# MB_Nano_V3_2.net
KiCad netlist of a schematic drawn in EAGLE
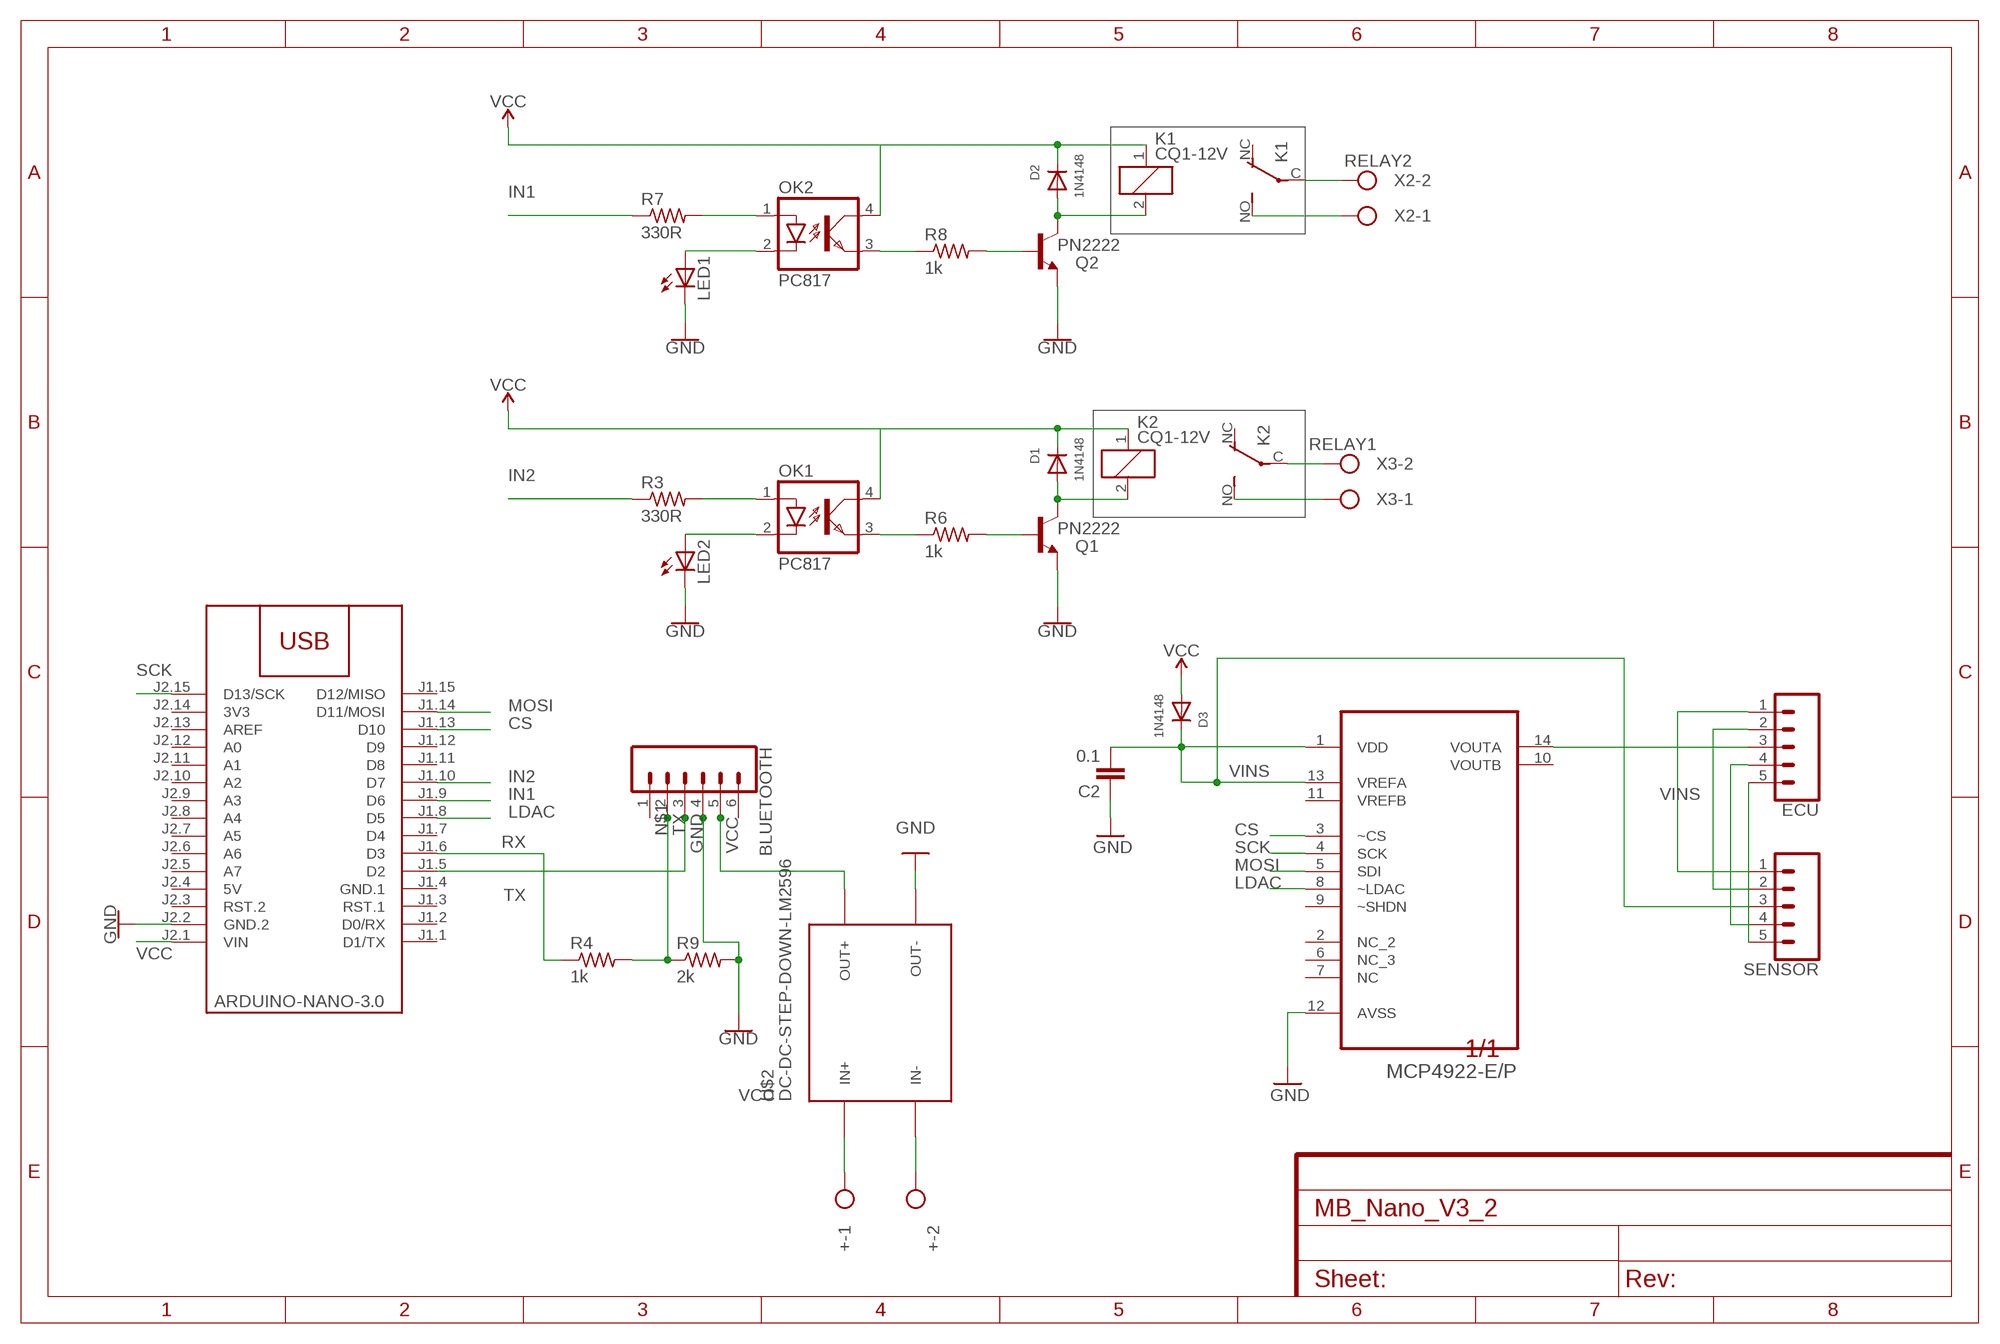
[diagram p0: schematic, sheet 1]

(export (version "E")
  (design (tool "Eeschema 10.0.6"))
  (components
    (comp (ref "+")
      (value "Vcc")
      (footprint "eagle-import:W237-102")
      (fields (field (name "MPN") "237-102"))
      (libsource (lib "eagle-import") (part "W237-102"))
    )
    (comp (ref "BLUETOOTH")
      (value "CONN_06LONGPADS")
      (footprint "eagle-import:1X06_LONGPADS")
      (libsource (lib "eagle-import") (part "CONN_06LONGPADS"))
    )
    (comp (ref "C2")
      (value "0.1")
      (footprint "eagle-import:CAP-PTH-5MM")
      (libsource (lib "eagle-import") (part "CAPPTH1"))
    )
    (comp (ref "D1")
      (value "1N4148")
      (footprint "eagle-import:DO-1N4148")
      (libsource (lib "eagle-import") (part "DIODEDO-1N4148"))
    )
    (comp (ref "D2")
      (value "1N4148")
      (footprint "eagle-import:DO-1N4148")
      (libsource (lib "eagle-import") (part "DIODEDO-1N4148"))
    )
    (comp (ref "D3")
      (value "1N4148")
      (footprint "eagle-import:DO-1N4148")
      (libsource (lib "eagle-import") (part "DIODEDO-1N4148"))
    )
    (comp (ref "ECU")
      (value "CONN_05PTH_LONGPADS")
      (footprint "eagle-import:1X05_LONGPADS")
      (libsource (lib "eagle-import") (part "CONN_05PTH_LONGPADS"))
    )
    (comp (ref "K1")
      (value "CQ1-12V")
      (footprint "eagle-import:CQ1")
      (libsource (lib "eagle-import") (part "CQ1-12V"))
    )
    (comp (ref "K2")
      (value "CQ1-12V")
      (footprint "eagle-import:CQ1")
      (libsource (lib "eagle-import") (part "CQ1-12V"))
    )
    (comp (ref "LED1")
      (value "LED3MM")
      (footprint "eagle-import:LED3MM")
      (libsource (lib "eagle-import") (part "LED3MM"))
    )
    (comp (ref "LED2")
      (value "LED3MM")
      (footprint "eagle-import:LED3MM")
      (libsource (lib "eagle-import") (part "LED3MM"))
    )
    (comp (ref "M2")
      (value "ARDUINO-NANO-3.0")
      (footprint "eagle-import:ARDUINO-NANO-3.0")
      (libsource (lib "eagle-import") (part "ARDUINO-NANO-3.0"))
    )
    (comp (ref "OK1")
      (value "PC817")
      (footprint "eagle-import:DIL04")
      (fields (field (name "MPN") "PC817X4J000F"))
      (libsource (lib "eagle-import") (part "PC817"))
    )
    (comp (ref "OK2")
      (value "PC817")
      (footprint "eagle-import:DIL04")
      (fields (field (name "MPN") "PC817X4J000F"))
      (libsource (lib "eagle-import") (part "PC817"))
    )
    (comp (ref "Q1")
      (value "PN2222")
      (footprint "eagle-import:TO92-EBC")
      (libsource (lib "eagle-import") (part "BC447"))
    )
    (comp (ref "Q2")
      (value "PN2222")
      (footprint "eagle-import:TO92-EBC")
      (libsource (lib "eagle-import") (part "BC447"))
    )
    (comp (ref "R3")
      (value "330R")
      (footprint "eagle-import:0204_7")
      (libsource (lib "eagle-import") (part "R-US_0204/7"))
    )
    (comp (ref "R4")
      (value "1k")
      (footprint "eagle-import:0204_7")
      (libsource (lib "eagle-import") (part "R-US_0204/7"))
    )
    (comp (ref "R6")
      (value "1k")
      (footprint "eagle-import:0204_7")
      (libsource (lib "eagle-import") (part "R-US_0204/7"))
    )
    (comp (ref "R7")
      (value "330R")
      (footprint "eagle-import:0204_7")
      (libsource (lib "eagle-import") (part "R-US_0204/7"))
    )
    (comp (ref "R8")
      (value "1k")
      (footprint "eagle-import:0204_7")
      (libsource (lib "eagle-import") (part "R-US_0204/7"))
    )
    (comp (ref "R9")
      (value "2k")
      (footprint "eagle-import:0204_7")
      (libsource (lib "eagle-import") (part "R-US_0204/7"))
    )
    (comp (ref "SENSOR")
      (value "CONN_05PTH_LONGPADS")
      (footprint "eagle-import:1X05_LONGPADS")
      (libsource (lib "eagle-import") (part "CONN_05PTH_LONGPADS"))
    )
    (comp (ref "U$2")
      (value "DC-DC-STEP-DOWN-LM2596")
      (footprint "eagle-import:DC-DC-STEP-DOWN-LM2596")
      (libsource (lib "eagle-import") (part "DC-DC-STEP-DOWN-LM2596"))
    )
    (comp (ref "U$3")
      (value "MCP4922-E/P")
      (footprint "eagle-import:DIP254P762X533-14")
      (libsource (lib "eagle-import") (part "MCP4922-E/P"))
    )
    (comp (ref "X2")
      (value "RELAY2")
      (footprint "eagle-import:W237-102")
      (fields (field (name "MPN") "237-102"))
      (libsource (lib "eagle-import") (part "W237-102"))
    )
    (comp (ref "X3")
      (value "RELAY1")
      (footprint "eagle-import:W237-102")
      (fields (field (name "MPN") "237-102"))
      (libsource (lib "eagle-import") (part "W237-102"))
    )
  )
  (nets
    (net (code "1") (name "/3V3") (class "Default")
      (node (ref "M2") (pin "J2.14") (pinfunction "3V3_J2.14") (pintype "power_in"))
    )
    (net (code "2") (name "/5V") (class "Default")
      (node (ref "M2") (pin "J2.4") (pinfunction "5V_J2.4") (pintype "power_in"))
    )
    (net (code "3") (name "/CS") (class "Default")
      (node (ref "M2") (pin "J1.13") (pinfunction "D10_J1.13") (pintype "bidirectional"))
      (node (ref "U$3") (pin "3") (pinfunction "~{CS}_3") (pintype "input"))
    )
    (net (code "4") (name "/GND.1") (class "Default")
      (node (ref "M2") (pin "J1.4") (pinfunction "GND.1_J1.4") (pintype "power_in"))
    )
    (net (code "5") (name "/IN1") (class "Default")
      (node (ref "M2") (pin "J1.9") (pinfunction "D6_J1.9") (pintype "bidirectional"))
      (node (ref "R7") (pin "1") (pinfunction "1_1") (pintype "passive"))
    )
    (net (code "6") (name "/IN2") (class "Default")
      (node (ref "M2") (pin "J1.10") (pinfunction "D7_J1.10") (pintype "bidirectional"))
      (node (ref "R3") (pin "1") (pinfunction "1_1") (pintype "passive"))
    )
    (net (code "7") (name "/LDAC") (class "Default")
      (node (ref "M2") (pin "J1.8") (pinfunction "D5_J1.8") (pintype "bidirectional"))
      (node (ref "U$3") (pin "8") (pinfunction "~{LDAC}_8") (pintype "input"))
    )
    (net (code "8") (name "/MOSI") (class "Default")
      (node (ref "M2") (pin "J1.14") (pinfunction "D11/MOSI_J1.14") (pintype "bidirectional"))
      (node (ref "U$3") (pin "5") (pinfunction "SDI_5") (pintype "input"))
    )
    (net (code "9") (name "/N$1") (class "Default")
      (node (ref "BLUETOOTH") (pin "2") (pinfunction "2_2") (pintype "passive"))
      (node (ref "R4") (pin "2") (pinfunction "2_2") (pintype "passive"))
      (node (ref "R9") (pin "1") (pinfunction "1_1") (pintype "passive"))
    )
    (net (code "10") (name "/RX") (class "Default")
      (node (ref "M2") (pin "J1.6") (pinfunction "D3_J1.6") (pintype "bidirectional"))
      (node (ref "R4") (pin "1") (pinfunction "1_1") (pintype "passive"))
    )
    (net (code "11") (name "/SCK") (class "Default")
      (node (ref "M2") (pin "J2.15") (pinfunction "D13/SCK_J2.15") (pintype "bidirectional"))
      (node (ref "U$3") (pin "4") (pinfunction "SCK_4") (pintype "input"))
    )
    (net (code "12") (name "/TX") (class "Default")
      (node (ref "BLUETOOTH") (pin "3") (pinfunction "3_3") (pintype "passive"))
      (node (ref "M2") (pin "J1.5") (pinfunction "D2_J1.5") (pintype "bidirectional"))
    )
    (net (code "13") (name "/VINS") (class "Default")
      (node (ref "C2") (pin "2") (pinfunction "2_2") (pintype "passive"))
      (node (ref "D3") (pin "C") (pinfunction "C_C") (pintype "passive"))
      (node (ref "SENSOR") (pin "3") (pinfunction "3_3") (pintype "passive"))
      (node (ref "U$3") (pin "1") (pinfunction "VDD_1") (pintype "power_in"))
      (node (ref "U$3") (pin "13") (pinfunction "VREFA_13") (pintype "input"))
    )
    (net (code "14") (name "GND") (class "Default")
      (node (ref "BLUETOOTH") (pin "4") (pinfunction "4_4") (pintype "passive"))
      (node (ref "C2") (pin "1") (pinfunction "1_1") (pintype "passive"))
      (node (ref "LED1") (pin "K") (pinfunction "C_K") (pintype "passive"))
      (node (ref "LED2") (pin "K") (pinfunction "C_K") (pintype "passive"))
      (node (ref "M2") (pin "J2.2") (pinfunction "GND.2_J2.2") (pintype "power_in"))
      (node (ref "Q1") (pin "E") (pinfunction "E_E") (pintype "passive"))
      (node (ref "Q2") (pin "E") (pinfunction "E_E") (pintype "passive"))
      (node (ref "R9") (pin "2") (pinfunction "2_2") (pintype "passive"))
      (node (ref "U$2") (pin "OUT-") (pinfunction "OUT-_OUT-") (pintype "bidirectional"))
      (node (ref "U$3") (pin "12") (pinfunction "AVSS_12") (pintype "power_in"))
    )
    (net (code "15") (name "Net-(+A-KL)") (class "Default")
      (node (ref "+") (pin "1") (pinfunction "KL_1") (pintype "passive"))
      (node (ref "U$2") (pin "IN+") (pinfunction "IN+_IN+") (pintype "bidirectional"))
    )
    (net (code "16") (name "Net-(+B-KL)") (class "Default")
      (node (ref "+") (pin "2") (pinfunction "KL_2") (pintype "passive"))
      (node (ref "U$2") (pin "IN-") (pinfunction "IN-_IN-") (pintype "bidirectional"))
    )
    (net (code "17") (name "Net-(D1-PadA)") (class "Default")
      (node (ref "D1") (pin "A") (pinfunction "A_A") (pintype "passive"))
      (node (ref "K2") (pin "2") (pinfunction "2_2") (pintype "passive"))
      (node (ref "Q1") (pin "C") (pinfunction "C_C") (pintype "passive"))
    )
    (net (code "18") (name "Net-(D2-PadA)") (class "Default")
      (node (ref "D2") (pin "A") (pinfunction "A_A") (pintype "passive"))
      (node (ref "K1") (pin "2") (pinfunction "2_2") (pintype "passive"))
      (node (ref "Q2") (pin "C") (pinfunction "C_C") (pintype "passive"))
    )
    (net (code "19") (name "Net-(ECU-Pad1)") (class "Default")
      (node (ref "ECU") (pin "1") (pinfunction "1_1") (pintype "passive"))
      (node (ref "SENSOR") (pin "1") (pinfunction "1_1") (pintype "passive"))
    )
    (net (code "20") (name "Net-(ECU-Pad2)") (class "Default")
      (node (ref "ECU") (pin "2") (pinfunction "2_2") (pintype "passive"))
      (node (ref "SENSOR") (pin "2") (pinfunction "2_2") (pintype "passive"))
    )
    (net (code "21") (name "Net-(ECU-Pad4)") (class "Default")
      (node (ref "ECU") (pin "4") (pinfunction "4_4") (pintype "passive"))
      (node (ref "SENSOR") (pin "4") (pinfunction "4_4") (pintype "passive"))
    )
    (net (code "22") (name "Net-(ECU-Pad5)") (class "Default")
      (node (ref "ECU") (pin "5") (pinfunction "5_5") (pintype "passive"))
      (node (ref "SENSOR") (pin "5") (pinfunction "5_5") (pintype "passive"))
    )
    (net (code "23") (name "Net-(K1B-P)") (class "Default")
      (node (ref "K1") (pin "C") (pinfunction "P_C") (pintype "passive"))
      (node (ref "X2") (pin "2") (pinfunction "KL_2") (pintype "passive"))
    )
    (net (code "24") (name "Net-(K1B-S)") (class "Default")
      (node (ref "K1") (pin "NO") (pinfunction "S_NO") (pintype "passive"))
      (node (ref "X2") (pin "1") (pinfunction "KL_1") (pintype "passive"))
    )
    (net (code "25") (name "Net-(K2B-P)") (class "Default")
      (node (ref "K2") (pin "C") (pinfunction "P_C") (pintype "passive"))
      (node (ref "X3") (pin "2") (pinfunction "KL_2") (pintype "passive"))
    )
    (net (code "26") (name "Net-(K2B-S)") (class "Default")
      (node (ref "K2") (pin "NO") (pinfunction "S_NO") (pintype "passive"))
      (node (ref "X3") (pin "1") (pinfunction "KL_1") (pintype "passive"))
    )
    (net (code "27") (name "Net-(OK1-A)") (class "Default")
      (node (ref "OK1") (pin "1") (pinfunction "A_1") (pintype "passive"))
      (node (ref "R3") (pin "2") (pinfunction "2_2") (pintype "passive"))
    )
    (net (code "28") (name "Net-(OK1-C)") (class "Default")
      (node (ref "LED2") (pin "A") (pinfunction "A_A") (pintype "passive"))
      (node (ref "OK1") (pin "2") (pinfunction "C_2") (pintype "passive"))
    )
    (net (code "29") (name "Net-(OK1-EMIT)") (class "Default")
      (node (ref "OK1") (pin "3") (pinfunction "EMIT_3") (pintype "passive"))
      (node (ref "R6") (pin "1") (pinfunction "1_1") (pintype "passive"))
    )
    (net (code "30") (name "Net-(OK2-A)") (class "Default")
      (node (ref "OK2") (pin "1") (pinfunction "A_1") (pintype "passive"))
      (node (ref "R7") (pin "2") (pinfunction "2_2") (pintype "passive"))
    )
    (net (code "31") (name "Net-(OK2-C)") (class "Default")
      (node (ref "LED1") (pin "A") (pinfunction "A_A") (pintype "passive"))
      (node (ref "OK2") (pin "2") (pinfunction "C_2") (pintype "passive"))
    )
    (net (code "32") (name "Net-(OK2-EMIT)") (class "Default")
      (node (ref "OK2") (pin "3") (pinfunction "EMIT_3") (pintype "passive"))
      (node (ref "R8") (pin "1") (pinfunction "1_1") (pintype "passive"))
    )
    (net (code "33") (name "Net-(Q1-PadB)") (class "Default")
      (node (ref "Q1") (pin "B") (pinfunction "B_B") (pintype "passive"))
      (node (ref "R6") (pin "2") (pinfunction "2_2") (pintype "passive"))
    )
    (net (code "34") (name "Net-(Q2-PadB)") (class "Default")
      (node (ref "Q2") (pin "B") (pinfunction "B_B") (pintype "passive"))
      (node (ref "R8") (pin "2") (pinfunction "2_2") (pintype "passive"))
    )
    (net (code "35") (name "Net-(U$3-VOUTA)") (class "Default")
      (node (ref "ECU") (pin "3") (pinfunction "3_3") (pintype "passive"))
      (node (ref "U$3") (pin "14") (pinfunction "VOUTA_14") (pintype "output"))
    )
    (net (code "36") (name "VCC") (class "Default")
      (node (ref "BLUETOOTH") (pin "5") (pinfunction "5_5") (pintype "passive"))
      (node (ref "D1") (pin "C") (pinfunction "C_C") (pintype "passive"))
      (node (ref "D2") (pin "C") (pinfunction "C_C") (pintype "passive"))
      (node (ref "D3") (pin "A") (pinfunction "A_A") (pintype "passive"))
      (node (ref "K1") (pin "1") (pinfunction "1_1") (pintype "passive"))
      (node (ref "K2") (pin "1") (pinfunction "1_1") (pintype "passive"))
      (node (ref "M2") (pin "J2.1") (pinfunction "VIN_J2.1") (pintype "power_in"))
      (node (ref "OK1") (pin "4") (pinfunction "COL_4") (pintype "passive"))
      (node (ref "OK2") (pin "4") (pinfunction "COL_4") (pintype "passive"))
      (node (ref "U$2") (pin "OUT+") (pinfunction "OUT+_OUT+") (pintype "bidirectional"))
    )
    (net (code "37") (name "unconnected-(BLUETOOTH-Pad1)") (class "Default")
      (node (ref "BLUETOOTH") (pin "1") (pinfunction "1_1") (pintype "passive"))
    )
    (net (code "38") (name "unconnected-(BLUETOOTH-Pad6)") (class "Default")
      (node (ref "BLUETOOTH") (pin "6") (pinfunction "6_6") (pintype "passive"))
    )
    (net (code "39") (name "unconnected-(K1B-O-PadNC)") (class "Default")
      (node (ref "K1") (pin "NC") (pinfunction "O_NC") (pintype "passive"))
    )
    (net (code "40") (name "unconnected-(K2B-O-PadNC)") (class "Default")
      (node (ref "K2") (pin "NC") (pinfunction "O_NC") (pintype "passive"))
    )
    (net (code "41") (name "unconnected-(M2-A0-PadJ2.12)") (class "Default")
      (node (ref "M2") (pin "J2.12") (pinfunction "A0_J2.12") (pintype "bidirectional"))
    )
    (net (code "42") (name "unconnected-(M2-A1-PadJ2.11)") (class "Default")
      (node (ref "M2") (pin "J2.11") (pinfunction "A1_J2.11") (pintype "bidirectional"))
    )
    (net (code "43") (name "unconnected-(M2-A2-PadJ2.10)") (class "Default")
      (node (ref "M2") (pin "J2.10") (pinfunction "A2_J2.10") (pintype "bidirectional"))
    )
    (net (code "44") (name "unconnected-(M2-A3-PadJ2.9)") (class "Default")
      (node (ref "M2") (pin "J2.9") (pinfunction "A3_J2.9") (pintype "bidirectional"))
    )
    (net (code "45") (name "unconnected-(M2-A4-PadJ2.8)") (class "Default")
      (node (ref "M2") (pin "J2.8") (pinfunction "A4_J2.8") (pintype "bidirectional"))
    )
    (net (code "46") (name "unconnected-(M2-A5-PadJ2.7)") (class "Default")
      (node (ref "M2") (pin "J2.7") (pinfunction "A5_J2.7") (pintype "bidirectional"))
    )
    (net (code "47") (name "unconnected-(M2-A6-PadJ2.6)") (class "Default")
      (node (ref "M2") (pin "J2.6") (pinfunction "A6_J2.6") (pintype "bidirectional"))
    )
    (net (code "48") (name "unconnected-(M2-A7-PadJ2.5)") (class "Default")
      (node (ref "M2") (pin "J2.5") (pinfunction "A7_J2.5") (pintype "bidirectional"))
    )
    (net (code "49") (name "unconnected-(M2-AREF-PadJ2.13)") (class "Default")
      (node (ref "M2") (pin "J2.13") (pinfunction "AREF_J2.13") (pintype "bidirectional"))
    )
    (net (code "50") (name "unconnected-(M2-D0{slash}RX-PadJ1.2)") (class "Default")
      (node (ref "M2") (pin "J1.2") (pinfunction "D0/RX_J1.2") (pintype "bidirectional"))
    )
    (net (code "51") (name "unconnected-(M2-D1{slash}TX-PadJ1.1)") (class "Default")
      (node (ref "M2") (pin "J1.1") (pinfunction "D1/TX_J1.1") (pintype "bidirectional"))
    )
    (net (code "52") (name "unconnected-(M2-D4-PadJ1.7)") (class "Default")
      (node (ref "M2") (pin "J1.7") (pinfunction "D4_J1.7") (pintype "bidirectional"))
    )
    (net (code "53") (name "unconnected-(M2-D8-PadJ1.11)") (class "Default")
      (node (ref "M2") (pin "J1.11") (pinfunction "D8_J1.11") (pintype "bidirectional"))
    )
    (net (code "54") (name "unconnected-(M2-D9-PadJ1.12)") (class "Default")
      (node (ref "M2") (pin "J1.12") (pinfunction "D9_J1.12") (pintype "bidirectional"))
    )
    (net (code "55") (name "unconnected-(M2-D12{slash}MISO-PadJ1.15)") (class "Default")
      (node (ref "M2") (pin "J1.15") (pinfunction "D12/MISO_J1.15") (pintype "bidirectional"))
    )
    (net (code "56") (name "unconnected-(M2-RST.1-PadJ1.3)") (class "Default")
      (node (ref "M2") (pin "J1.3") (pinfunction "RST.1_J1.3") (pintype "bidirectional"))
    )
    (net (code "57") (name "unconnected-(M2-RST.2-PadJ2.3)") (class "Default")
      (node (ref "M2") (pin "J2.3") (pinfunction "RST.2_J2.3") (pintype "bidirectional"))
    )
    (net (code "58") (name "unconnected-(U$3-NC-Pad7)") (class "Default")
      (node (ref "U$3") (pin "7") (pinfunction "NC_7") (pintype "no_connect"))
    )
    (net (code "59") (name "unconnected-(U$3-NC_2-Pad2)") (class "Default")
      (node (ref "U$3") (pin "2") (pinfunction "NC_2_2") (pintype "no_connect"))
    )
    (net (code "60") (name "unconnected-(U$3-NC_3-Pad6)") (class "Default")
      (node (ref "U$3") (pin "6") (pinfunction "NC_3_6") (pintype "no_connect"))
    )
    (net (code "61") (name "unconnected-(U$3-VOUTB-Pad10)") (class "Default")
      (node (ref "U$3") (pin "10") (pinfunction "VOUTB_10") (pintype "output"))
    )
    (net (code "62") (name "unconnected-(U$3-VREFB-Pad11)") (class "Default")
      (node (ref "U$3") (pin "11") (pinfunction "VREFB_11") (pintype "input"))
    )
    (net (code "63") (name "unconnected-(U$3-~{SHDN}-Pad9)") (class "Default")
      (node (ref "U$3") (pin "9") (pinfunction "~{SHDN}_9") (pintype "input"))
    )
  )
)
